# timer.net
KiCad netlist of a schematic drawn in EAGLE
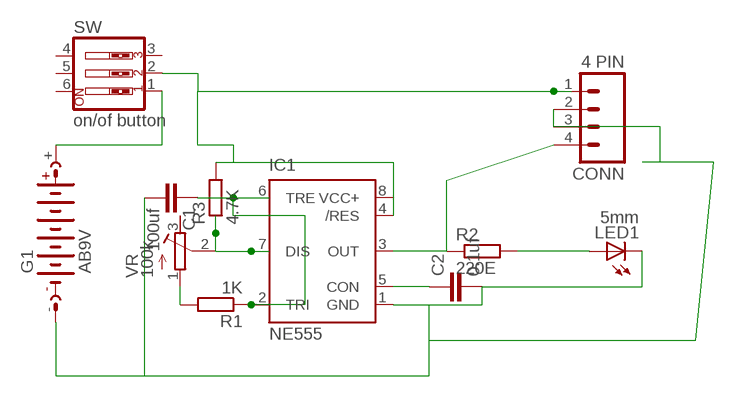
[diagram p0: schematic, sheet 1]

(export (version "E")
  (design (tool "Eeschema 10.0.6"))
  (components
    (comp (ref "C1")
      (value "100uf")
      (footprint "eagle-import:C025-050X050")
      (libsource (lib "eagle-import") (part "C-EU025-050X050"))
    )
    (comp (ref "C2")
      (value "0.1uf")
      (footprint "eagle-import:C025-050X050")
      (libsource (lib "eagle-import") (part "C-EU025-050X050"))
    )
    (comp (ref "CONN")
      (value "4 PIN")
      (footprint "eagle-import:04P")
      (libsource (lib "eagle-import") (part "M04"))
    )
    (comp (ref "G1")
      (value "AB9V")
      (footprint "eagle-import:AB9V")
      (libsource (lib "eagle-import") (part "AB9V"))
    )
    (comp (ref "IC1")
      (value "NE555")
      (footprint "eagle-import:DIL-08")
      (fields (field (name "MF") "Arrow Electronics") (field (name "MPN") "NE555N"))
      (libsource (lib "eagle-import") (part "NE555"))
    )
    (comp (ref "LED1")
      (value "5mm")
      (footprint "eagle-import:LED5MM")
      (libsource (lib "eagle-import") (part "LED5MM"))
    )
    (comp (ref "R1")
      (value "1K")
      (footprint "eagle-import:0204_7")
      (libsource (lib "eagle-import") (part "R-EU_0204/7"))
    )
    (comp (ref "R2")
      (value "220E")
      (footprint "eagle-import:0204_7")
      (libsource (lib "eagle-import") (part "R-EU_0204/7"))
    )
    (comp (ref "R3")
      (value "4.7K")
      (footprint "eagle-import:0204_7")
      (libsource (lib "eagle-import") (part "R-EU_0204/7"))
    )
    (comp (ref "SW")
      (value "on/of button")
      (footprint "eagle-import:EDG-03")
      (libsource (lib "eagle-import") (part "SW_DIP-3"))
    )
    (comp (ref "VR")
      (value "100k")
      (footprint "eagle-import:RTRIM64P")
      (libsource (lib "eagle-import") (part "R-TRIMM64P"))
    )
  )
  (nets
    (net (code "1") (name "Net-(G1-Pad+)") (class "Default")
      (node (ref "G1") (pin "+") (pinfunction "+_+") (pintype "passive"))
      (node (ref "SW") (pin "1") (pinfunction "1_1") (pintype "passive"))
    )
    (net (code "2") (name "Net-(IC1-CON)") (class "Default")
      (node (ref "C2") (pin "1") (pinfunction "1_1") (pintype "passive"))
      (node (ref "IC1") (pin "5") (pinfunction "CON_5") (pintype "input"))
    )
    (net (code "3") (name "Net-(IC1-DIS)") (class "Default")
      (node (ref "IC1") (pin "7") (pinfunction "DIS_7") (pintype "input"))
      (node (ref "R3") (pin "1") (pinfunction "1_1") (pintype "passive"))
      (node (ref "VR") (pin "2") (pinfunction "S_2") (pintype "passive"))
    )
    (net (code "4") (name "Net-(IC1-GND)") (class "Default")
      (node (ref "C1") (pin "2") (pinfunction "2_2") (pintype "passive"))
      (node (ref "C2") (pin "2") (pinfunction "2_2") (pintype "passive"))
      (node (ref "CONN") (pin "2") (pinfunction "2_2") (pintype "passive"))
      (node (ref "CONN") (pin "3") (pinfunction "3_3") (pintype "passive"))
      (node (ref "G1") (pin "-") (pinfunction "-_-") (pintype "passive"))
      (node (ref "IC1") (pin "1") (pinfunction "GND_1") (pintype "power_in"))
      (node (ref "LED1") (pin "K") (pinfunction "C_K") (pintype "passive"))
    )
    (net (code "5") (name "Net-(IC1-OUT)") (class "Default")
      (node (ref "CONN") (pin "4") (pinfunction "4_4") (pintype "passive"))
      (node (ref "IC1") (pin "3") (pinfunction "OUT_3") (pintype "output"))
      (node (ref "R2") (pin "1") (pinfunction "1_1") (pintype "passive"))
    )
    (net (code "6") (name "Net-(IC1-TRE)") (class "Default")
      (node (ref "C1") (pin "1") (pinfunction "1_1") (pintype "passive"))
      (node (ref "IC1") (pin "2") (pinfunction "TRI_2") (pintype "input"))
      (node (ref "IC1") (pin "6") (pinfunction "TRE_6") (pintype "input"))
      (node (ref "R1") (pin "1") (pinfunction "1_1") (pintype "passive"))
    )
    (net (code "7") (name "Net-(IC1-VCC+)") (class "Default")
      (node (ref "CONN") (pin "1") (pinfunction "1_1") (pintype "passive"))
      (node (ref "IC1") (pin "4") (pinfunction "/RES_4") (pintype "input"))
      (node (ref "IC1") (pin "8") (pinfunction "VCC+_8") (pintype "power_in"))
      (node (ref "R3") (pin "2") (pinfunction "2_2") (pintype "passive"))
      (node (ref "SW") (pin "2") (pinfunction "2_2") (pintype "passive"))
    )
    (net (code "8") (name "Net-(LED1-PadA)") (class "Default")
      (node (ref "LED1") (pin "A") (pinfunction "A_A") (pintype "passive"))
      (node (ref "R2") (pin "2") (pinfunction "2_2") (pintype "passive"))
    )
    (net (code "9") (name "Net-(VR-E)") (class "Default")
      (node (ref "R1") (pin "2") (pinfunction "2_2") (pintype "passive"))
      (node (ref "VR") (pin "1") (pinfunction "E_1") (pintype "passive"))
    )
    (net (code "10") (name "unconnected-(SW-Pad3)") (class "Default")
      (node (ref "SW") (pin "3") (pinfunction "3_3") (pintype "passive"))
    )
    (net (code "11") (name "unconnected-(SW-Pad4)") (class "Default")
      (node (ref "SW") (pin "4") (pinfunction "4_4") (pintype "passive"))
    )
    (net (code "12") (name "unconnected-(SW-Pad5)") (class "Default")
      (node (ref "SW") (pin "5") (pinfunction "5_5") (pintype "passive"))
    )
    (net (code "13") (name "unconnected-(SW-Pad6)") (class "Default")
      (node (ref "SW") (pin "6") (pinfunction "6_6") (pintype "passive"))
    )
    (net (code "14") (name "unconnected-(VR-A-Pad3)") (class "Default")
      (node (ref "VR") (pin "3") (pinfunction "A_3") (pintype "passive"))
    )
  )
)
